# Executive_12V_A.net
KiCad netlist of a schematic drawn in EAGLE
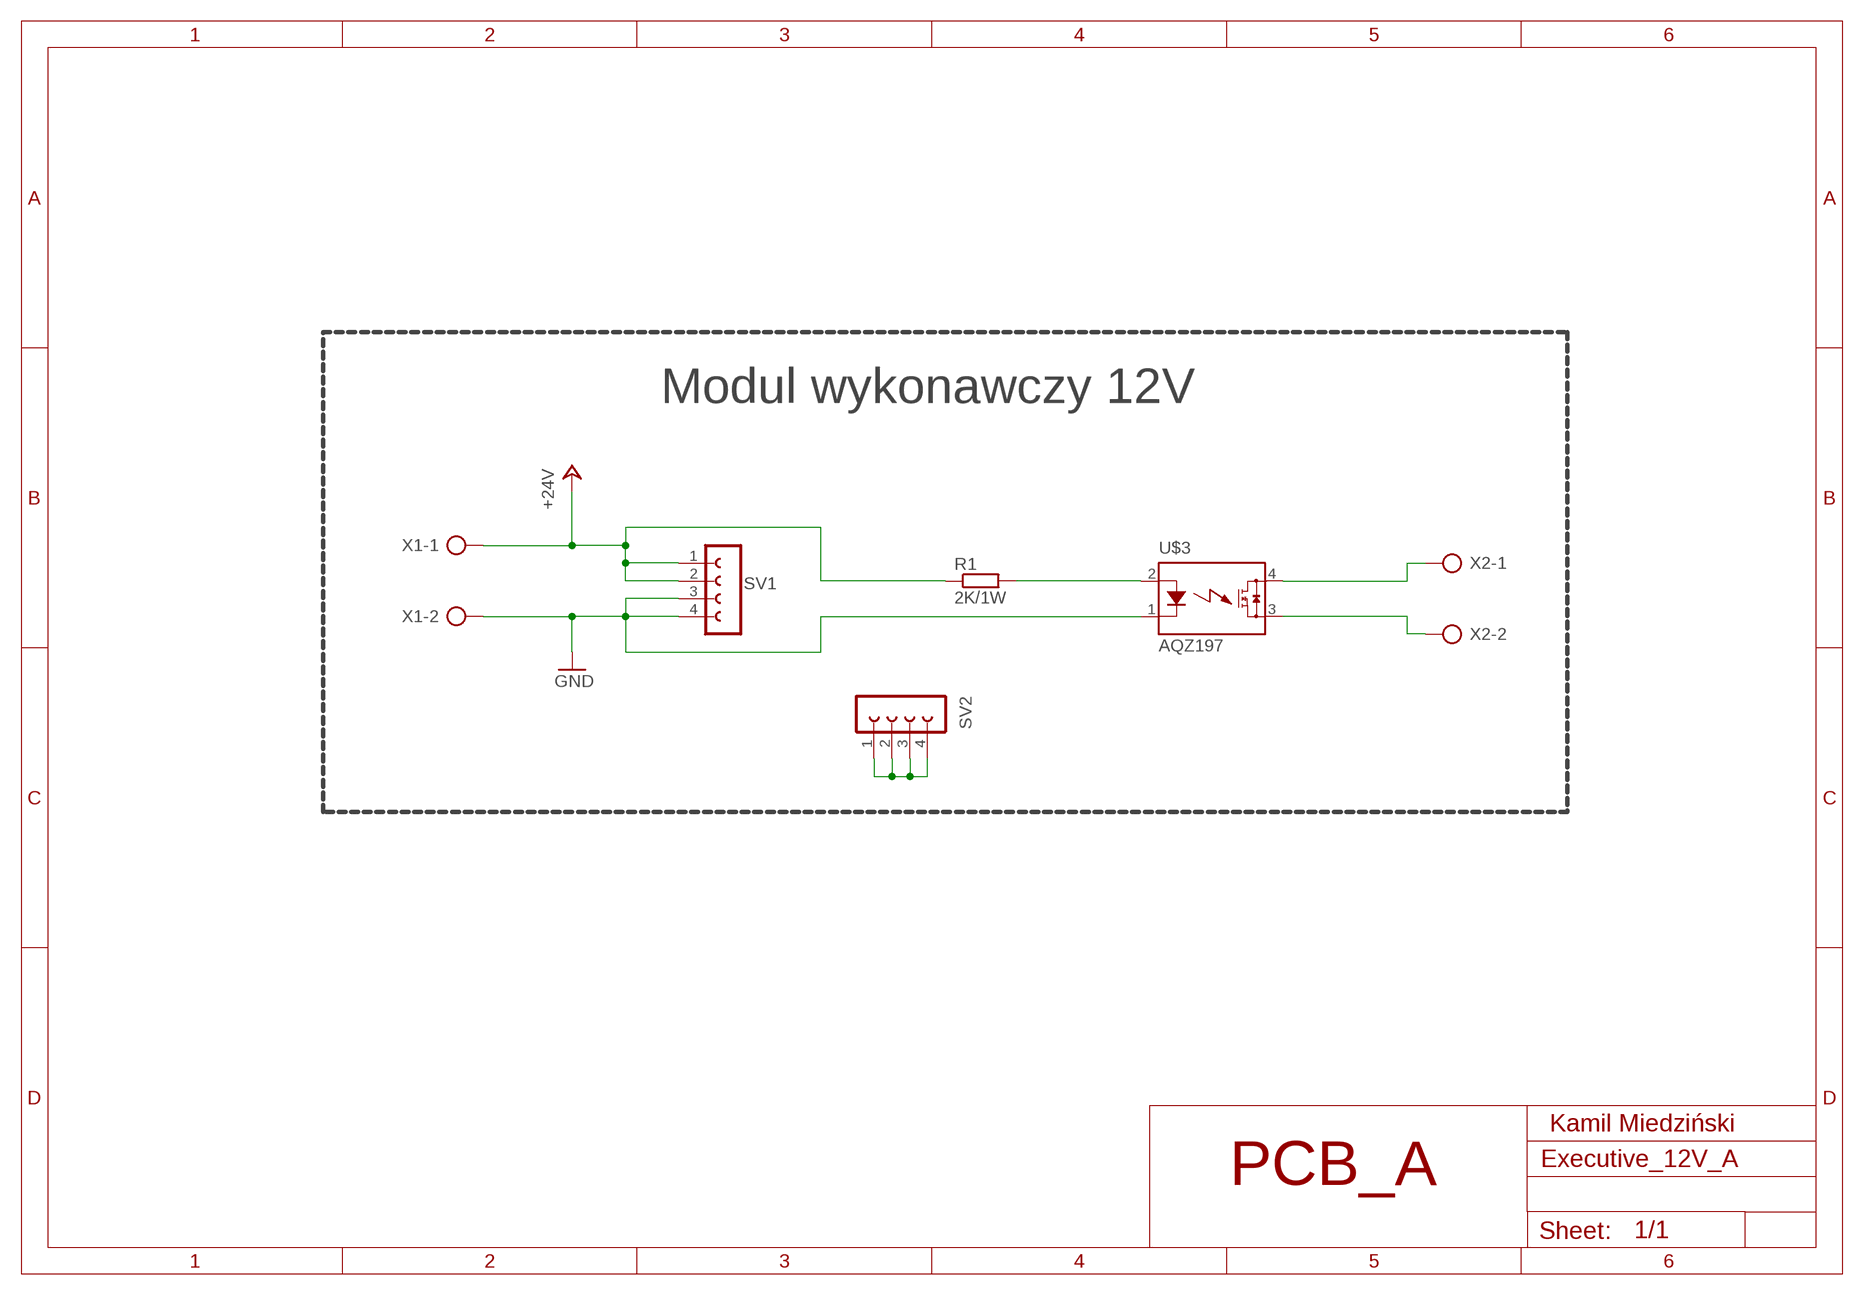
[diagram p0: schematic, sheet 1]

(export (version "E")
  (design (tool "Eeschema 10.0.6"))
  (components
    (comp (ref "R1")
      (value "2K/1W")
      (footprint "eagle-import:0411_15")
      (libsource (lib "eagle-import") (part "R-EU_0411/15"))
    )
    (comp (ref "SV1")
      (value "FE04-1")
      (footprint "eagle-import:FE04-1")
      (libsource (lib "eagle-import") (part "FE04-1"))
    )
    (comp (ref "SV2")
      (value "FE04-1")
      (footprint "eagle-import:FE04-1")
      (libsource (lib "eagle-import") (part "FE04-1"))
    )
    (comp (ref "U$3")
      (value "AQZ197")
      (footprint "eagle-import:AQZ-SIL04")
      (libsource (lib "eagle-import") (part "AQZ197"))
    )
    (comp (ref "X1")
      (value "GMKDSP_3/2")
      (footprint "eagle-import:GMKDSP_3_2")
      (libsource (lib "eagle-import") (part "GMKDSP_3/2"))
    )
    (comp (ref "X2")
      (value "GMKDSP_3/2")
      (footprint "eagle-import:GMKDSP_3_2")
      (libsource (lib "eagle-import") (part "GMKDSP_3/2"))
    )
  )
  (nets
    (net (code "1") (name "+24V") (class "Default")
      (node (ref "R1") (pin "1") (pinfunction "1_1") (pintype "passive"))
      (node (ref "SV1") (pin "1") (pinfunction "2_1") (pintype "passive"))
      (node (ref "SV1") (pin "2") (pinfunction "3_2") (pintype "passive"))
      (node (ref "X1") (pin "1") (pinfunction "KL_1") (pintype "passive"))
    )
    (net (code "2") (name "GND") (class "Default")
      (node (ref "SV1") (pin "3") (pinfunction "4_3") (pintype "passive"))
      (node (ref "SV1") (pin "4") (pinfunction "5_4") (pintype "passive"))
      (node (ref "U$3") (pin "1") (pinfunction "K_1") (pintype "passive"))
      (node (ref "X1") (pin "2") (pinfunction "KL_2") (pintype "passive"))
    )
    (net (code "3") (name "Net-(SV2-2)") (class "Default")
      (node (ref "SV2") (pin "1") (pinfunction "2_1") (pintype "passive"))
      (node (ref "SV2") (pin "2") (pinfunction "3_2") (pintype "passive"))
      (node (ref "SV2") (pin "3") (pinfunction "4_3") (pintype "passive"))
      (node (ref "SV2") (pin "4") (pinfunction "5_4") (pintype "passive"))
    )
    (net (code "4") (name "Net-(U$3-A)") (class "Default")
      (node (ref "R1") (pin "2") (pinfunction "2_2") (pintype "passive"))
      (node (ref "U$3") (pin "2") (pinfunction "A_2") (pintype "passive"))
    )
    (net (code "5") (name "Net-(U$3-DS1)") (class "Default")
      (node (ref "U$3") (pin "4") (pinfunction "DS1_4") (pintype "passive"))
      (node (ref "X2") (pin "1") (pinfunction "KL_1") (pintype "passive"))
    )
    (net (code "6") (name "Net-(U$3-DS2)") (class "Default")
      (node (ref "U$3") (pin "3") (pinfunction "DS2_3") (pintype "passive"))
      (node (ref "X2") (pin "2") (pinfunction "KL_2") (pintype "passive"))
    )
  )
)
